# pmic_tps51386_buck.net
KiCad netlist of a schematic drawn in Altium Designer
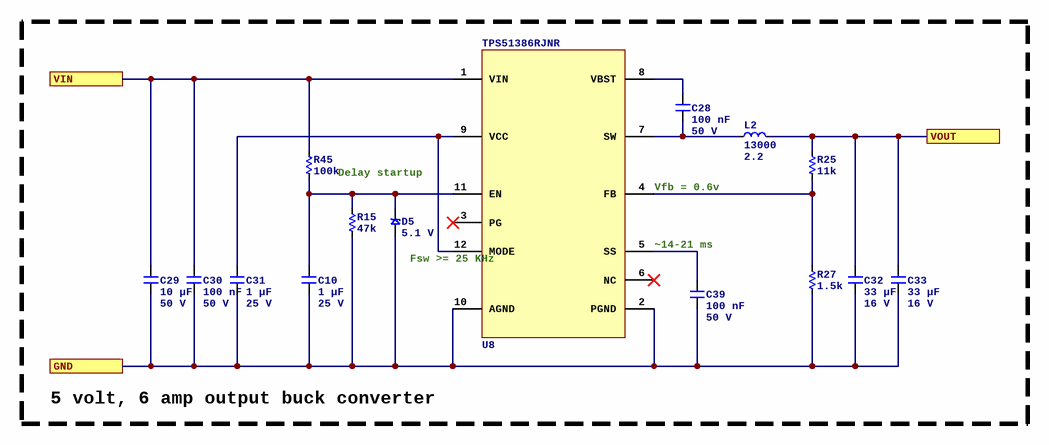
[diagram p0: pmic_tps51386_buck.SchDoc]

(export (version "E")
  (design (tool "Eeschema 10.0.6"))
  (components
    (comp (ref "C10")
      (value "CL10B105KA8NNNC")
      (footprint "C0603")
      (fields
        (field (name "CAPACITANCE") "1 µF")
        (field (name "MANUFACTURER") "Samsung Electro-Mechanics")
        (field (name "VOLTAGE RATING") "25 V")
      )
      (libsource (lib "database") (part "__template_cap"))
    )
    (comp (ref "C28")
      (value "CL05B104KB54PNC")
      (footprint "C0402")
      (fields
        (field (name "CAPACITANCE") "100 nF")
        (field (name "MANUFACTURER") "Samsung Electro-Mechanics")
        (field (name "VOLTAGE RATING") "50 V")
      )
      (libsource (lib "database") (part "__template_cap"))
    )
    (comp (ref "C29")
      (value "CL31B106KBHNNNE")
      (footprint "C1206")
      (fields
        (field (name "CAPACITANCE") "10 µF")
        (field (name "MANUFACTURER") "Samsung Electro-Mechanics")
        (field (name "VOLTAGE RATING") "50 V")
      )
      (libsource (lib "database") (part "__template_cap"))
    )
    (comp (ref "C30")
      (value "CL05B104KB54PNC")
      (footprint "C0402")
      (fields
        (field (name "CAPACITANCE") "100 nF")
        (field (name "MANUFACTURER") "Samsung Electro-Mechanics")
        (field (name "VOLTAGE RATING") "50 V")
      )
      (libsource (lib "database") (part "__template_cap"))
    )
    (comp (ref "C31")
      (value "CL10B105KA8NNNC")
      (footprint "C0603")
      (fields
        (field (name "CAPACITANCE") "1 µF")
        (field (name "MANUFACTURER") "Samsung Electro-Mechanics")
        (field (name "VOLTAGE RATING") "25 V")
      )
      (libsource (lib "database") (part "__template_cap"))
    )
    (comp (ref "C32")
      (value "C4532X7R1C336MT000N")
      (footprint "C1812")
      (fields
        (field (name "CAPACITANCE") "33 µF")
        (field (name "MANUFACTURER") "TDK")
        (field (name "VOLTAGE RATING") "16 V")
      )
      (libsource (lib "database") (part "__template_cap"))
    )
    (comp (ref "C33")
      (value "C4532X7R1C336MT000N")
      (footprint "C1812")
      (fields
        (field (name "CAPACITANCE") "33 µF")
        (field (name "MANUFACTURER") "TDK")
        (field (name "VOLTAGE RATING") "16 V")
      )
      (libsource (lib "database") (part "__template_cap"))
    )
    (comp (ref "C39")
      (value "CL05B104KB54PNC")
      (footprint "C0402")
      (fields
        (field (name "CAPACITANCE") "100 nF")
        (field (name "MANUFACTURER") "Samsung Electro-Mechanics")
        (field (name "VOLTAGE RATING") "50 V")
      )
      (libsource (lib "database") (part "__template_cap"))
    )
    (comp (ref "D5")
      (value "SZMM3Z5V1ST1G")
      (footprint "SOD323")
      (description "Zener Diode 5.1 V 300 mW ±2% Surface Mount SOD-323")
      (fields (field (name "MANUFACTURER") "onsemi") (field (name "VR") "5.1 V"))
      (libsource (lib "database") (part "__template_diode_zener"))
    )
    (comp (ref "L2")
      (value "SRP7030CA-2R2M")
      (footprint "BOURNS_SRP7030CA")
      (description "2.2 µH shielded power inductor")
      (fields
        (field (name "MANUFACTURER") "BOURNS")
        (field (name "CURRENT RATING (MA)") "13000")
        (field (name "INDUCTANCE (ΜH)") "2.2")
      )
      (libsource (lib "database") (part "__template_inductor"))
    )
    (comp (ref "R15")
      (value "47k")
      (footprint "R0402")
      (fields
        (field (name "TOLERANCE") "1%")
        (field (name "MANUFACTURER PART NUMBER") "0402WGF4702TCE")
        (field (name "MANUFACTURER") "UNI-ROYAL(Uniroyal Elec)")
      )
      (libsource (lib "database") (part "__template_resistor"))
    )
    (comp (ref "R25")
      (value "11k")
      (footprint "R0402")
      (fields
        (field (name "MANUFACTURER PART NUMBER") "0402WGF1102TCE")
        (field (name "MANUFACTURER") "UNI-ROYAL(Uniroyal Elec)")
        (field (name "TOLERANCE") "1%")
      )
      (libsource (lib "database") (part "__template_resistor"))
    )
    (comp (ref "R27")
      (value "1.5k")
      (footprint "R0402")
      (fields
        (field (name "TOLERANCE") "1%")
        (field (name "MANUFACTURER PART NUMBER") "0402WGF1501TCE")
        (field (name "MANUFACTURER") "UNI-ROYAL(Uniroyal Elec)")
      )
      (libsource (lib "database") (part "__template_resistor"))
    )
    (comp (ref "R45")
      (value "100k")
      (footprint "R0402")
      (fields
        (field (name "TOLERANCE") "1%")
        (field (name "MANUFACTURER PART NUMBER") "0402WGF1003TCE")
        (field (name "MANUFACTURER") "UNI-ROYAL(Uniroyal Elec)")
      )
      (libsource (lib "database") (part "__template_resistor"))
    )
    (comp (ref "U8")
      (value "TPS51386RJNR")
      (footprint "TI_RJN")
      (description "Buck Switching Regulator IC Positive Adjustable 0.6V 1 Output 8A 12-PowerVFQFN")
      (fields (field (name "MANUFACTURER") "Texas Instruments"))
      (libsource (lib "database") (part "TPS51386RJNR"))
    )
  )
  (nets
    (net (code "1") (name "/GND") (class "Default")
      (node (ref "C10") (pin "2") (pintype "passive"))
      (node (ref "C29") (pin "2") (pintype "passive"))
      (node (ref "C30") (pin "2") (pintype "passive"))
      (node (ref "C31") (pin "2") (pintype "passive"))
      (node (ref "C32") (pin "2") (pintype "passive"))
      (node (ref "C33") (pin "2") (pintype "passive"))
      (node (ref "C39") (pin "2") (pintype "passive"))
      (node (ref "D5") (pin "1") (pintype "passive"))
      (node (ref "R15") (pin "2") (pintype "passive"))
      (node (ref "R27") (pin "2") (pintype "passive"))
      (node (ref "U8") (pin "10") (pinfunction "AGND_10") (pintype "passive"))
      (node (ref "U8") (pin "2") (pinfunction "PGND_2") (pintype "passive"))
    )
    (net (code "2") (name "/VIN") (class "Default")
      (node (ref "C29") (pin "1") (pintype "passive"))
      (node (ref "C30") (pin "1") (pintype "passive"))
      (node (ref "R45") (pin "1") (pintype "passive"))
      (node (ref "U8") (pin "1") (pinfunction "VIN_1") (pintype "passive"))
    )
    (net (code "3") (name "/VOUT") (class "Default")
      (node (ref "C32") (pin "1") (pintype "passive"))
      (node (ref "C33") (pin "1") (pintype "passive"))
      (node (ref "L2") (pin "2") (pintype "passive"))
      (node (ref "R25") (pin "2") (pintype "passive"))
    )
    (net (code "4") (name "Net-(U8-EN)") (class "Default")
      (node (ref "C10") (pin "1") (pintype "passive"))
      (node (ref "D5") (pin "2") (pintype "passive"))
      (node (ref "R15") (pin "1") (pintype "passive"))
      (node (ref "R45") (pin "2") (pintype "passive"))
      (node (ref "U8") (pin "11") (pinfunction "EN_11") (pintype "passive"))
    )
    (net (code "5") (name "Net-(U8-FB)") (class "Default")
      (node (ref "R25") (pin "1") (pintype "passive"))
      (node (ref "R27") (pin "1") (pintype "passive"))
      (node (ref "U8") (pin "4") (pinfunction "FB_4") (pintype "passive"))
    )
    (net (code "6") (name "Net-(U8-MODE)") (class "Default")
      (node (ref "C31") (pin "1") (pintype "passive"))
      (node (ref "U8") (pin "12") (pinfunction "MODE_12") (pintype "passive"))
      (node (ref "U8") (pin "9") (pinfunction "VCC_9") (pintype "passive"))
    )
    (net (code "7") (name "Net-(U8-SS)") (class "Default")
      (node (ref "C39") (pin "1") (pintype "passive"))
      (node (ref "U8") (pin "5") (pinfunction "SS_5") (pintype "passive"))
    )
    (net (code "8") (name "Net-(U8-SW)") (class "Default")
      (node (ref "C28") (pin "2") (pintype "passive"))
      (node (ref "L2") (pin "1") (pintype "passive"))
      (node (ref "U8") (pin "7") (pinfunction "SW_7") (pintype "passive"))
    )
    (net (code "9") (name "Net-(U8-VBST)") (class "Default")
      (node (ref "C28") (pin "1") (pintype "passive"))
      (node (ref "U8") (pin "8") (pinfunction "VBST_8") (pintype "passive"))
    )
    (net (code "10") (name "unconnected-(U8-NC-Pad6)") (class "Default")
      (node (ref "U8") (pin "6") (pinfunction "NC_6") (pintype "passive+no_connect"))
    )
    (net (code "11") (name "unconnected-(U8-PG-Pad3)") (class "Default")
      (node (ref "U8") (pin "3") (pinfunction "PG_3") (pintype "passive+no_connect"))
    )
  )
)
